# MMI.net
KiCad netlist of a schematic drawn in Altium Designer
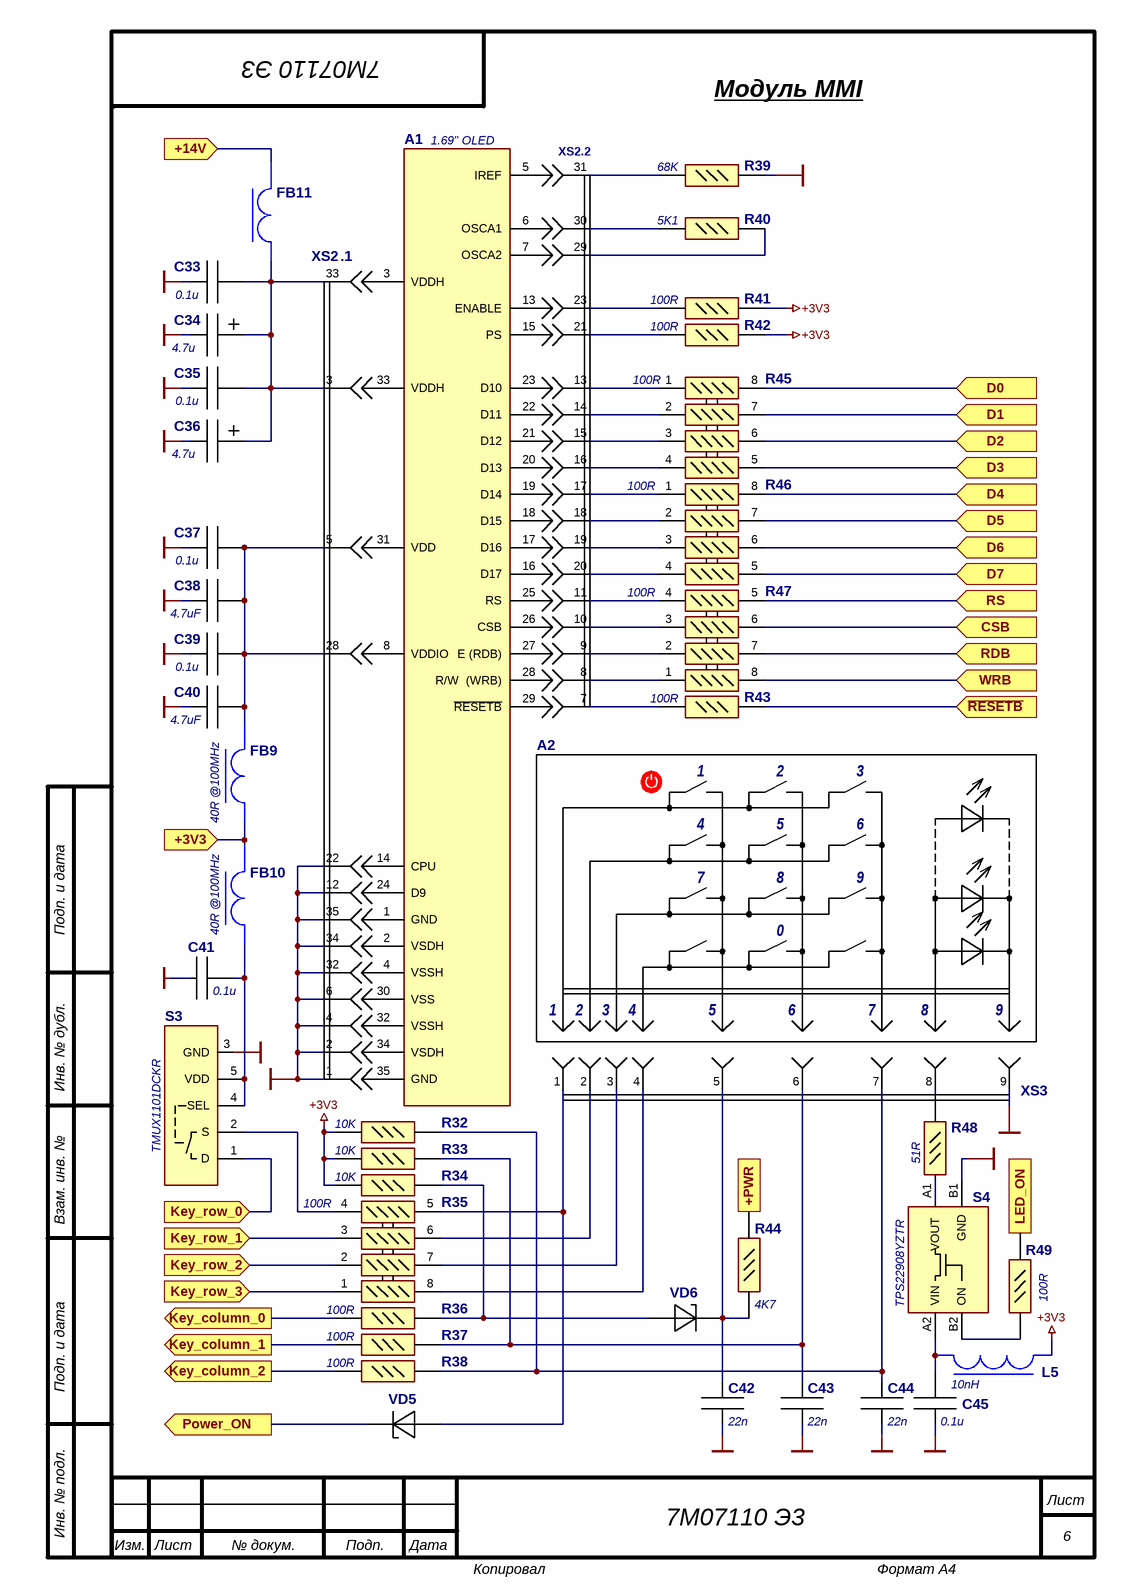
[diagram p0: Модуль MMI.SchDoc]

(export (version "E")
  (design (tool "Eeschema 10.0.6"))
  (components
    (comp (ref "A1")
      (value "1.69\" OLED")
      (fields (field (name "MANUFACTURER_PART_NUMBER") "NHD-1.69-160128G"))
      (libsource (lib "Other") (part "NHD-1.69-160128G"))
    )
    (comp (ref "A2")
      (value "~")
      (fields (field (name "MANUFACTURER_PART_NUMBER") "Клавиатура 5042 ТЕИЯ.464511.002 ТЗ"))
      (libsource (lib "Other") (part "Клавиатура 3x4 (Заказ №...)"))
    )
    (comp (ref "C33")
      (value "0.1u")
      (footprint ":CAP0402 100x50x50")
      (description "±10% 25V Ceramic Capacitor X7R 0402 (1005 Metric)")
      (fields
        (field (name "MANUFACTURER_PART_NUMBER") "GRM155R71E104KE14J")
        (field (name "MOUSER PART NUMBER") "81-GRM155R71E104KE4J")
      )
      (libsource (lib "Capacitors 0402") (part "GRM155R71E104KE14J"))
    )
    (comp (ref "C34")
      (value "4.7u")
      (footprint ":CAP1206 C3216-18")
      (description "4.7µF Molded Tantalum Capacitors 25V 1206 (3216 Metric) 50mOhm")
      (fields (field (name "MANUFACTURER_PART_NUMBER") "T491A475K025AT"))
      (libsource (lib "Capacitors 1206") (part "T491A475K025AT"))
    )
    (comp (ref "C35")
      (value "0.1u")
      (footprint ":CAP0402 100x50x50")
      (description "±10% 25V Ceramic Capacitor X7R 0402 (1005 Metric)")
      (fields
        (field (name "MANUFACTURER_PART_NUMBER") "GRM155R71E104KE14J")
        (field (name "MOUSER PART NUMBER") "81-GRM155R71E104KE4J")
      )
      (libsource (lib "Capacitors 0402") (part "GRM155R71E104KE14J"))
    )
    (comp (ref "C36")
      (value "4.7u")
      (footprint ":CAP1206 C3216-18")
      (description "4.7µF Molded Tantalum Capacitors 25V 1206 (3216 Metric) 50mOhm")
      (fields (field (name "MANUFACTURER_PART_NUMBER") "T491A475K025AT"))
      (libsource (lib "Capacitors 1206") (part "T491A475K025AT"))
    )
    (comp (ref "C37")
      (value "0.1u")
      (footprint ":CAP0402 100x50x50")
      (description "±10% 25V Ceramic Capacitor X7R 0402 (1005 Metric)")
      (fields
        (field (name "MANUFACTURER_PART_NUMBER") "GRM155R71E104KE14J")
        (field (name "MOUSER PART NUMBER") "81-GRM155R71E104KE4J")
      )
      (libsource (lib "Capacitors 0402") (part "GRM155R71E104KE14J"))
    )
    (comp (ref "C38")
      (value "4.7uF")
      (footprint ":CAP0805 C2012X125")
      (description "CAP CER 4.7uF 25V X7R 0805")
      (fields (field (name "MANUFACTURER_PART_NUMBER") "GRM21BZ71E475KE15L"))
      (libsource (lib "Capacitors 0805") (part "GRM21BZ71E475KE15L"))
    )
    (comp (ref "C39")
      (value "0.1u")
      (footprint ":CAP0402 100x50x50")
      (description "±10% 25V Ceramic Capacitor X7R 0402 (1005 Metric)")
      (fields
        (field (name "MANUFACTURER_PART_NUMBER") "GRM155R71E104KE14J")
        (field (name "MOUSER PART NUMBER") "81-GRM155R71E104KE4J")
      )
      (libsource (lib "Capacitors 0402") (part "GRM155R71E104KE14J"))
    )
    (comp (ref "C40")
      (value "4.7uF")
      (footprint ":CAP0805 C2012X125")
      (description "CAP CER 4.7uF 25V X7R 0805")
      (fields (field (name "MANUFACTURER_PART_NUMBER") "GRM21BZ71E475KE15L"))
      (libsource (lib "Capacitors 0805") (part "GRM21BZ71E475KE15L"))
    )
    (comp (ref "C41")
      (value "0.1u")
      (footprint ":CAP0402 100x50x50")
      (description "±10% 25V Ceramic Capacitor X7R 0402 (1005 Metric)")
      (fields
        (field (name "MANUFACTURER_PART_NUMBER") "GRM155R71E104KE14J")
        (field (name "MOUSER PART NUMBER") "81-GRM155R71E104KE4J")
      )
      (libsource (lib "Capacitors 0402") (part "GRM155R71E104KE14J"))
    )
    (comp (ref "C42")
      (value "22n")
      (footprint ":CAP0402 100x50x50")
      (description "CAP CER  25V X7R 0402")
      (fields (field (name "MANUFACTURER_PART_NUMBER") "GCM155R71E223KA55D"))
      (libsource (lib "Capacitors 0402") (part "GCM155R71E223KA55D"))
    )
    (comp (ref "C43")
      (value "22n")
      (footprint ":CAP0402 100x50x50")
      (description "CAP CER  25V X7R 0402")
      (fields (field (name "MANUFACTURER_PART_NUMBER") "GCM155R71E223KA55D"))
      (libsource (lib "Capacitors 0402") (part "GCM155R71E223KA55D"))
    )
    (comp (ref "C44")
      (value "22n")
      (footprint ":CAP0402 100x50x50")
      (description "CAP CER  25V X7R 0402")
      (fields (field (name "MANUFACTURER_PART_NUMBER") "GCM155R71E223KA55D"))
      (libsource (lib "Capacitors 0402") (part "GCM155R71E223KA55D"))
    )
    (comp (ref "C45")
      (value "0.1u")
      (footprint ":CAP0402 100x50x50")
      (description "±10% 25V Ceramic Capacitor X7R 0402 (1005 Metric)")
      (fields
        (field (name "MANUFACTURER_PART_NUMBER") "GRM155R71E104KE14J")
        (field (name "MOUSER PART NUMBER") "81-GRM155R71E104KE4J")
      )
      (libsource (lib "Capacitors 0402") (part "GRM155R71E104KE14J"))
    )
    (comp (ref "FB9")
      (value "40R @100MHz")
      (footprint ":FER MMZ1005Y400CTD25")
      (description "40 Ohms @ 100MHz 1 Signal Line Ferrite Bead 0402 (1005 Metric) 550mA 100mOhm")
      (fields
        (field (name "MANUFACTURER_PART_NUMBER") "MMZ1005Y400CTD25")
        (field (name "MOUSER PART NUMBER") "810-MMZ1005Y400CTD25")
      )
      (libsource (lib "Ferrite Bead") (part "MMZ1005Y400CTD25"))
    )
    (comp (ref "FB10")
      (value "40R @100MHz")
      (footprint ":FER MMZ1005Y400CTD25")
      (description "40 Ohms @ 100MHz 1 Signal Line Ferrite Bead 0402 (1005 Metric) 550mA 100mOhm")
      (fields
        (field (name "MANUFACTURER_PART_NUMBER") "MMZ1005Y400CTD25")
        (field (name "MOUSER PART NUMBER") "810-MMZ1005Y400CTD25")
      )
      (libsource (lib "Ferrite Bead") (part "MMZ1005Y400CTD25"))
    )
    (comp (ref "FB11")
      (value "40R @100MHz")
      (footprint ":FER MMZ1005Y400CTD25")
      (description "40 Ohms @ 100MHz 1 Signal Line Ferrite Bead 0402 (1005 Metric) 550mA 100mOhm")
      (fields
        (field (name "MANUFACTURER_PART_NUMBER") "MMZ1005Y400CTD25")
        (field (name "MOUSER PART NUMBER") "810-MMZ1005Y400CTD25")
      )
      (libsource (lib "Ferrite Bead") (part "MMZ1005Y400CTD25"))
    )
    (comp (ref "L5")
      (value "10nH")
      (footprint ":IND 0402")
      (description "Unshielded Multilayer Inductor 0402 5%")
      (fields (field (name "MANUFACTURER_PART_NUMBER") "LQG15HN10NJ02D"))
      (libsource (lib "Inductance 0402") (part "LQG15HN10NJ02D"))
    )
    (comp (ref "R32")
      (value "RC0402FR-07")
      (footprint ":RES0402")
      (fields (field (name "MANUFACTURER_PART_NUMBER (PART 2: VALUE)") "10K"))
      (libsource (lib "") (part "RC0402FR-07_1"))
    )
    (comp (ref "R33")
      (value "RC0402FR-07")
      (footprint ":RES0402")
      (fields (field (name "MANUFACTURER_PART_NUMBER (PART 2: VALUE)") "10K"))
      (libsource (lib "") (part "RC0402FR-07_1"))
    )
    (comp (ref "R34")
      (value "RC0402FR-07")
      (footprint ":RES0402")
      (fields (field (name "MANUFACTURER_PART_NUMBER (PART 2: VALUE)") "10K"))
      (libsource (lib "") (part "RC0402FR-07_1"))
    )
    (comp (ref "R35")
      (value "100R")
      (footprint ":RES0402x4")
      (fields
        (field (name "MANUFACTURER_PART_NUMBER") "EXB-N8V101JX")
        (field (name "MOUSER PART NUMBER") "667-EXB-N8V101JX")
      )
      (libsource (lib "") (part "EXB-N8V101JX_1"))
    )
    (comp (ref "R36")
      (value "RC0402FR-07")
      (footprint ":RES0402")
      (fields (field (name "MANUFACTURER_PART_NUMBER (PART 2: VALUE)") "100R"))
      (libsource (lib "Resistors 0402") (part "RC0402FR-07"))
    )
    (comp (ref "R37")
      (value "RC0402FR-07")
      (footprint ":RES0402")
      (fields (field (name "MANUFACTURER_PART_NUMBER (PART 2: VALUE)") "100R"))
      (libsource (lib "Resistors 0402") (part "RC0402FR-07"))
    )
    (comp (ref "R38")
      (value "RC0402FR-07")
      (footprint ":RES0402")
      (fields (field (name "MANUFACTURER_PART_NUMBER (PART 2: VALUE)") "100R"))
      (libsource (lib "Resistors 0402") (part "RC0402FR-07"))
    )
    (comp (ref "R39")
      (value "RC0402FR-07")
      (footprint ":RES0402")
      (fields (field (name "MANUFACTURER_PART_NUMBER (PART 2: VALUE)") "68K"))
      (libsource (lib "Resistors 0402") (part "RC0402FR-07"))
    )
    (comp (ref "R40")
      (value "RC0402FR-07")
      (footprint ":RES0402")
      (fields (field (name "MANUFACTURER_PART_NUMBER (PART 2: VALUE)") "5K1"))
      (libsource (lib "Resistors 0402") (part "RC0402FR-07"))
    )
    (comp (ref "R41")
      (value "RC0402FR-07")
      (footprint ":RES0402")
      (fields (field (name "MANUFACTURER_PART_NUMBER (PART 2: VALUE)") "100R"))
      (libsource (lib "Resistors 0402") (part "RC0402FR-07"))
    )
    (comp (ref "R42")
      (value "RC0402FR-07")
      (footprint ":RES0402")
      (fields (field (name "MANUFACTURER_PART_NUMBER (PART 2: VALUE)") "100R"))
      (libsource (lib "Resistors 0402") (part "RC0402FR-07"))
    )
    (comp (ref "R43")
      (value "RC0402FR-07")
      (footprint ":RES0402")
      (fields (field (name "MANUFACTURER_PART_NUMBER (PART 2: VALUE)") "100R"))
      (libsource (lib "Resistors 0402") (part "RC0402FR-07"))
    )
    (comp (ref "R44")
      (value "RC0402FR-07")
      (footprint ":RES0402")
      (fields (field (name "MANUFACTURER_PART_NUMBER (PART 2: VALUE)") "4K7"))
      (libsource (lib "") (part "RC0402FR-07_2"))
    )
    (comp (ref "R45")
      (value "100R")
      (footprint ":RES0402x4")
      (fields
        (field (name "MANUFACTURER_PART_NUMBER") "EXB-N8V101JX")
        (field (name "MOUSER PART NUMBER") "667-EXB-N8V101JX")
      )
      (libsource (lib "Resistors Arrays") (part "EXB-N8V101JX"))
    )
    (comp (ref "R46")
      (value "100R")
      (footprint ":RES0402x4")
      (fields
        (field (name "MANUFACTURER_PART_NUMBER") "EXB-N8V101JX")
        (field (name "MOUSER PART NUMBER") "667-EXB-N8V101JX")
      )
      (libsource (lib "Resistors Arrays") (part "EXB-N8V101JX"))
    )
    (comp (ref "R47")
      (value "100R")
      (footprint ":RES0402x4")
      (fields
        (field (name "MANUFACTURER_PART_NUMBER") "EXB-N8V101JX")
        (field (name "MOUSER PART NUMBER") "667-EXB-N8V101JX")
      )
      (libsource (lib "") (part "EXB-N8V101JX_1"))
    )
    (comp (ref "R48")
      (value "RC0402FR-07")
      (footprint ":RES0402")
      (fields (field (name "MANUFACTURER_PART_NUMBER (PART 2: VALUE)") "51R"))
      (libsource (lib "") (part "RC0402FR-07_2"))
    )
    (comp (ref "R49")
      (value "RC0402FR-07")
      (footprint ":RES0402")
      (fields (field (name "MANUFACTURER_PART_NUMBER (PART 2: VALUE)") "100R"))
      (libsource (lib "") (part "RC0402FR-07_2"))
    )
    (comp (ref "S3")
      (value "TMUX1101DCKR")
      (footprint ":SC70 (5) P200X125X10")
      (description "SPST Switch Bidir. 1.8 Ω 30mA 300MHz")
      (fields (field (name "MOUSER PART NUMBER") "595-TMUX1101DCKR"))
      (libsource (lib "Switching and Relays") (part "TMUX1101DCKR"))
    )
    (comp (ref "S4")
      (value "TPS22908YZTR")
      (footprint ":BGA4 P90X90X50")
      (description "SPST Switch 3.6-V, 1-A, 28-mΩ")
      (fields (field (name "MOUSER PART NUMBER") "595-TPS22908YZTR"))
      (libsource (lib "Switching and Relays") (part "TPS22908YZTR"))
    )
    (comp (ref "VD5")
      (value "30V 0.1A")
      (footprint ":DIODE SOD-923F")
      (description "Diodes Schottky 0402 30V 0.1A")
      (fields
        (field (name "MANUFACTURER_PART_NUMBER") "CDBQR0130R")
        (field (name "MOUSER PART NUMBER") "750-CDBQR0130R")
      )
      (libsource (lib "Diodes 0402") (part "CDBQR0130R"))
    )
    (comp (ref "VD6")
      (value "30V 0.1A")
      (footprint ":DIODE SOD-923F")
      (description "Diodes Schottky 0402 30V 0.1A")
      (fields
        (field (name "MANUFACTURER_PART_NUMBER") "CDBQR0130R")
        (field (name "MOUSER PART NUMBER") "750-CDBQR0130R")
      )
      (libsource (lib "Diodes 0402") (part "CDBQR0130R"))
    )
    (comp (ref "XS2")
      (value "0541043531")
      (footprint "ZIK lib:541043531")
      (description "Rotary Backlock Connector 35-pin 0.5mm Pitch, Top side Contact")
      (fields (field (name "MOUSER2 PART NUMBER") "538-54104-3531"))
      (libsource (lib "Connectors") (part "0541043531"))
    )
    (comp (ref "XS3")
      (value "XF3M-0915-1B")
      (footprint ":CON XF3M-0915-1B")
      (description "Rotary Backlock Connector 35-pin 0.5mm Pitch, Dual sided Contact")
      (libsource (lib "Connectors") (part "XF3M-0915-1B"))
    )
  )
  (nets
    (net (code "1") (name "+3V3") (class "Default")
      (node (ref "FB10") (pin "2") (pinfunction "2_2") (pintype "passive"))
      (node (ref "FB9") (pin "1") (pinfunction "1_1") (pintype "passive"))
      (node (ref "L5") (pin "2") (pinfunction "2_2") (pintype "passive"))
      (node (ref "R32") (pin "2") (pinfunction "2_2") (pintype "passive"))
      (node (ref "R33") (pin "2") (pinfunction "2_2") (pintype "passive"))
      (node (ref "R34") (pin "2") (pinfunction "2_2") (pintype "passive"))
      (node (ref "R41") (pin "2") (pinfunction "2_2") (pintype "passive"))
      (node (ref "R42") (pin "2") (pinfunction "2_2") (pintype "passive"))
    )
    (net (code "2") (name "/+14V") (class "Default")
      (node (ref "FB11") (pin "2") (pinfunction "2_2") (pintype "passive"))
    )
    (net (code "3") (name "/+PWR") (class "Default")
      (node (ref "R44") (pin "1") (pinfunction "1_1") (pintype "passive"))
    )
    (net (code "4") (name "/CSB") (class "Default")
      (node (ref "R47") (pin "6") (pinfunction "6_6") (pintype "passive"))
    )
    (net (code "5") (name "/D0") (class "Default")
      (node (ref "R45") (pin "8") (pinfunction "8_8") (pintype "passive"))
    )
    (net (code "6") (name "/D1") (class "Default")
      (node (ref "R45") (pin "7") (pinfunction "7_7") (pintype "passive"))
    )
    (net (code "7") (name "/D2") (class "Default")
      (node (ref "R45") (pin "6") (pinfunction "6_6") (pintype "passive"))
    )
    (net (code "8") (name "/D3") (class "Default")
      (node (ref "R45") (pin "5") (pinfunction "5_5") (pintype "passive"))
    )
    (net (code "9") (name "/D4") (class "Default")
      (node (ref "R46") (pin "8") (pinfunction "8_8") (pintype "passive"))
    )
    (net (code "10") (name "/D5") (class "Default")
      (node (ref "R46") (pin "7") (pinfunction "7_7") (pintype "passive"))
    )
    (net (code "11") (name "/D6") (class "Default")
      (node (ref "R46") (pin "6") (pinfunction "6_6") (pintype "passive"))
    )
    (net (code "12") (name "/D7") (class "Default")
      (node (ref "R46") (pin "5") (pinfunction "5_5") (pintype "passive"))
    )
    (net (code "13") (name "/Key_column_0") (class "Default")
      (node (ref "R36") (pin "1") (pinfunction "1_1") (pintype "passive"))
    )
    (net (code "14") (name "/Key_column_1") (class "Default")
      (node (ref "R37") (pin "1") (pinfunction "1_1") (pintype "passive"))
    )
    (net (code "15") (name "/Key_column_2") (class "Default")
      (node (ref "R38") (pin "1") (pinfunction "1_1") (pintype "passive"))
    )
    (net (code "16") (name "/Key_row_0") (class "Default")
      (node (ref "S3") (pin "1") (pinfunction "D_1") (pintype "passive"))
    )
    (net (code "17") (name "/Key_row_1") (class "Default")
      (node (ref "R35") (pin "3") (pinfunction "3_3") (pintype "passive"))
    )
    (net (code "18") (name "/Key_row_2") (class "Default")
      (node (ref "R35") (pin "2") (pinfunction "2_2") (pintype "passive"))
    )
    (net (code "19") (name "/Key_row_3") (class "Default")
      (node (ref "R35") (pin "1") (pinfunction "1_1") (pintype "passive"))
    )
    (net (code "20") (name "/LED_ON") (class "Default")
      (node (ref "R49") (pin "1") (pinfunction "1_1") (pintype "passive"))
    )
    (net (code "21") (name "/Power_ON") (class "Default")
      (node (ref "VD5") (pin "1") (pinfunction "K_1") (pintype "passive"))
    )
    (net (code "22") (name "/RDB") (class "Default")
      (node (ref "R47") (pin "7") (pinfunction "7_7") (pintype "passive"))
    )
    (net (code "23") (name "/RS") (class "Default")
      (node (ref "R47") (pin "5") (pinfunction "5_5") (pintype "passive"))
    )
    (net (code "24") (name "/WRB") (class "Default")
      (node (ref "R47") (pin "8") (pinfunction "8_8") (pintype "passive"))
    )
    (net (code "25") (name "/~{RESETB}") (class "Default")
      (node (ref "R43") (pin "2") (pinfunction "2_2") (pintype "passive"))
    )
    (net (code "26") (name "GND") (class "Default")
      (node (ref "C33") (pin "1") (pinfunction "1_1") (pintype "passive"))
      (node (ref "C34") (pin "2") (pinfunction "2_2") (pintype "passive"))
      (node (ref "C35") (pin "1") (pinfunction "1_1") (pintype "passive"))
      (node (ref "C36") (pin "2") (pinfunction "2_2") (pintype "passive"))
      (node (ref "C37") (pin "1") (pinfunction "1_1") (pintype "passive"))
      (node (ref "C38") (pin "2") (pinfunction "2_2") (pintype "passive"))
      (node (ref "C39") (pin "1") (pinfunction "1_1") (pintype "passive"))
      (node (ref "C40") (pin "2") (pinfunction "2_2") (pintype "passive"))
      (node (ref "C41") (pin "1") (pinfunction "1_1") (pintype "passive"))
      (node (ref "C42") (pin "1") (pinfunction "1_1") (pintype "passive"))
      (node (ref "C43") (pin "1") (pinfunction "1_1") (pintype "passive"))
      (node (ref "C44") (pin "1") (pinfunction "1_1") (pintype "passive"))
      (node (ref "C45") (pin "2") (pinfunction "2_2") (pintype "passive"))
      (node (ref "R39") (pin "2") (pinfunction "2_2") (pintype "passive"))
      (node (ref "S3") (pin "3") (pinfunction "GND_3") (pintype "passive"))
      (node (ref "S4") (pin "B1") (pinfunction "GND_B1") (pintype "passive"))
      (node (ref "XS2") (pin "1") (pintype "passive"))
      (node (ref "XS2") (pin "12") (pintype "passive"))
      (node (ref "XS2") (pin "2") (pintype "passive"))
      (node (ref "XS2") (pin "22") (pintype "passive"))
      (node (ref "XS2") (pin "32") (pintype "passive"))
      (node (ref "XS2") (pin "34") (pintype "passive"))
      (node (ref "XS2") (pin "35") (pintype "passive"))
      (node (ref "XS2") (pin "4") (pintype "passive"))
      (node (ref "XS2") (pin "6") (pintype "passive"))
      (node (ref "XS3") (pin "9") (pinfunction "9_9") (pintype "passive"))
    )
    (net (code "27") (name "Net-(C34-+)") (class "Default")
      (node (ref "C33") (pin "2") (pinfunction "2_2") (pintype "passive"))
      (node (ref "C34") (pin "1") (pinfunction "+_1") (pintype "passive"))
      (node (ref "C35") (pin "2") (pinfunction "2_2") (pintype "passive"))
      (node (ref "C36") (pin "1") (pinfunction "+_1") (pintype "passive"))
      (node (ref "FB11") (pin "1") (pinfunction "1_1") (pintype "passive"))
      (node (ref "XS2") (pin "3") (pintype "passive"))
      (node (ref "XS2") (pin "33") (pintype "passive"))
    )
    (net (code "28") (name "Net-(C37-Pad2)") (class "Default")
      (node (ref "C37") (pin "2") (pinfunction "2_2") (pintype "passive"))
      (node (ref "C38") (pin "1") (pinfunction "1_1") (pintype "passive"))
      (node (ref "C39") (pin "2") (pinfunction "2_2") (pintype "passive"))
      (node (ref "C40") (pin "1") (pinfunction "1_1") (pintype "passive"))
      (node (ref "FB9") (pin "2") (pinfunction "2_2") (pintype "passive"))
      (node (ref "XS2") (pin "28") (pintype "passive"))
      (node (ref "XS2") (pin "5") (pintype "passive"))
    )
    (net (code "29") (name "Net-(C43-Pad2)") (class "Default")
      (node (ref "C43") (pin "2") (pinfunction "2_2") (pintype "passive"))
      (node (ref "R33") (pin "1") (pinfunction "1_1") (pintype "passive"))
      (node (ref "R37") (pin "2") (pinfunction "2_2") (pintype "passive"))
      (node (ref "XS3") (pin "6") (pinfunction "6_6") (pintype "passive"))
    )
    (net (code "30") (name "Net-(C44-Pad2)") (class "Default")
      (node (ref "C44") (pin "2") (pinfunction "2_2") (pintype "passive"))
      (node (ref "R32") (pin "1") (pinfunction "1_1") (pintype "passive"))
      (node (ref "R38") (pin "2") (pinfunction "2_2") (pintype "passive"))
      (node (ref "XS3") (pin "7") (pinfunction "7_7") (pintype "passive"))
    )
    (net (code "31") (name "Net-(R35-Pad7)") (class "Default")
      (node (ref "R35") (pin "7") (pinfunction "7_7") (pintype "passive"))
      (node (ref "XS3") (pin "3") (pinfunction "3_3") (pintype "passive"))
    )
    (net (code "32") (name "Net-(R35-Pad8)") (class "Default")
      (node (ref "R35") (pin "8") (pinfunction "8_8") (pintype "passive"))
      (node (ref "XS3") (pin "4") (pinfunction "4_4") (pintype "passive"))
    )
    (net (code "33") (name "Net-(R39-Pad1)") (class "Default")
      (node (ref "R39") (pin "1") (pinfunction "1_1") (pintype "passive"))
      (node (ref "XS2") (pin "31") (pintype "passive"))
    )
    (net (code "34") (name "Net-(R40-Pad1)") (class "Default")
      (node (ref "R40") (pin "1") (pinfunction "1_1") (pintype "passive"))
      (node (ref "XS2") (pin "30") (pintype "passive"))
    )
    (net (code "35") (name "Net-(R40-Pad2)") (class "Default")
      (node (ref "R40") (pin "2") (pinfunction "2_2") (pintype "passive"))
      (node (ref "XS2") (pin "29") (pintype "passive"))
    )
    (net (code "36") (name "Net-(R41-Pad1)") (class "Default")
      (node (ref "R41") (pin "1") (pinfunction "1_1") (pintype "passive"))
      (node (ref "XS2") (pin "23") (pintype "passive"))
    )
    (net (code "37") (name "Net-(R42-Pad1)") (class "Default")
      (node (ref "R42") (pin "1") (pinfunction "1_1") (pintype "passive"))
      (node (ref "XS2") (pin "21") (pintype "passive"))
    )
    (net (code "38") (name "Net-(R43-Pad1)") (class "Default")
      (node (ref "R43") (pin "1") (pinfunction "1_1") (pintype "passive"))
      (node (ref "XS2") (pin "7") (pintype "passive"))
    )
    (net (code "39") (name "Net-(R45-Pad1)") (class "Default")
      (node (ref "R45") (pin "1") (pinfunction "1_1") (pintype "passive"))
      (node (ref "XS2") (pin "13") (pintype "passive"))
    )
    (net (code "40") (name "Net-(R45-Pad2)") (class "Default")
      (node (ref "R45") (pin "2") (pinfunction "2_2") (pintype "passive"))
      (node (ref "XS2") (pin "14") (pintype "passive"))
    )
    (net (code "41") (name "Net-(R45-Pad3)") (class "Default")
      (node (ref "R45") (pin "3") (pinfunction "3_3") (pintype "passive"))
      (node (ref "XS2") (pin "15") (pintype "passive"))
    )
    (net (code "42") (name "Net-(R45-Pad4)") (class "Default")
      (node (ref "R45") (pin "4") (pinfunction "4_4") (pintype "passive"))
      (node (ref "XS2") (pin "16") (pintype "passive"))
    )
    (net (code "43") (name "Net-(R46-Pad1)") (class "Default")
      (node (ref "R46") (pin "1") (pinfunction "1_1") (pintype "passive"))
      (node (ref "XS2") (pin "17") (pintype "passive"))
    )
    (net (code "44") (name "Net-(R46-Pad2)") (class "Default")
      (node (ref "R46") (pin "2") (pinfunction "2_2") (pintype "passive"))
      (node (ref "XS2") (pin "18") (pintype "passive"))
    )
    (net (code "45") (name "Net-(R46-Pad3)") (class "Default")
      (node (ref "R46") (pin "3") (pinfunction "3_3") (pintype "passive"))
      (node (ref "XS2") (pin "19") (pintype "passive"))
    )
    (net (code "46") (name "Net-(R46-Pad4)") (class "Default")
      (node (ref "R46") (pin "4") (pinfunction "4_4") (pintype "passive"))
      (node (ref "XS2") (pin "20") (pintype "passive"))
    )
    (net (code "47") (name "Net-(R47-Pad1)") (class "Default")
      (node (ref "R47") (pin "1") (pinfunction "1_1") (pintype "passive"))
      (node (ref "XS2") (pin "8") (pintype "passive"))
    )
    (net (code "48") (name "Net-(R47-Pad2)") (class "Default")
      (node (ref "R47") (pin "2") (pinfunction "2_2") (pintype "passive"))
      (node (ref "XS2") (pin "9") (pintype "passive"))
    )
    (net (code "49") (name "Net-(R47-Pad3)") (class "Default")
      (node (ref "R47") (pin "3") (pinfunction "3_3") (pintype "passive"))
      (node (ref "XS2") (pin "10") (pintype "passive"))
    )
    (net (code "50") (name "Net-(R47-Pad4)") (class "Default")
      (node (ref "R47") (pin "4") (pinfunction "4_4") (pintype "passive"))
      (node (ref "XS2") (pin "11") (pintype "passive"))
    )
    (net (code "51") (name "Net-(R48-Pad1)") (class "Default")
      (node (ref "R48") (pin "1") (pinfunction "1_1") (pintype "passive"))
      (node (ref "XS3") (pin "8") (pinfunction "8_8") (pintype "passive"))
    )
    (net (code "52") (name "Net-(S3-S)") (class "Default")
      (node (ref "R35") (pin "4") (pinfunction "4_4") (pintype "passive"))
      (node (ref "S3") (pin "2") (pinfunction "S_2") (pintype "passive"))
    )
    (net (code "53") (name "Net-(S3-SEL)") (class "Default")
      (node (ref "C41") (pin "2") (pinfunction "2_2") (pintype "passive"))
      (node (ref "FB10") (pin "1") (pinfunction "1_1") (pintype "passive"))
      (node (ref "S3") (pin "4") (pinfunction "SEL_4") (pintype "passive"))
      (node (ref "S3") (pin "5") (pinfunction "VDD_5") (pintype "passive"))
    )
    (net (code "54") (name "Net-(S4-ON)") (class "Default")
      (node (ref "R49") (pin "2") (pinfunction "2_2") (pintype "passive"))
      (node (ref "S4") (pin "B2") (pinfunction "ON_B2") (pintype "passive"))
    )
    (net (code "55") (name "Net-(S4-VIN)") (class "Default")
      (node (ref "C45") (pin "1") (pinfunction "1_1") (pintype "passive"))
      (node (ref "L5") (pin "1") (pinfunction "1_1") (pintype "passive"))
      (node (ref "S4") (pin "A2") (pinfunction "VIN_A2") (pintype "passive"))
    )
    (net (code "56") (name "Net-(S4-VOUT)") (class "Default")
      (node (ref "R48") (pin "2") (pinfunction "2_2") (pintype "passive"))
      (node (ref "S4") (pin "A1") (pinfunction "VOUT_A1") (pintype "passive"))
    )
    (net (code "57") (name "Net-(VD5-A)") (class "Default")
      (node (ref "R35") (pin "5") (pinfunction "5_5") (pintype "passive"))
      (node (ref "VD5") (pin "2") (pinfunction "A_2") (pintype "passive"))
      (node (ref "XS3") (pin "1") (pinfunction "1_1") (pintype "passive"))
    )
    (net (code "58") (name "Net-(VD6-A)") (class "Default")
      (node (ref "R34") (pin "1") (pinfunction "1_1") (pintype "passive"))
      (node (ref "R36") (pin "2") (pinfunction "2_2") (pintype "passive"))
      (node (ref "VD6") (pin "2") (pinfunction "A_2") (pintype "passive"))
    )
    (net (code "59") (name "Net-(VD6-K)") (class "Default")
      (node (ref "C42") (pin "2") (pinfunction "2_2") (pintype "passive"))
      (node (ref "R44") (pin "2") (pinfunction "2_2") (pintype "passive"))
      (node (ref "VD6") (pin "1") (pinfunction "K_1") (pintype "passive"))
      (node (ref "XS3") (pin "5") (pinfunction "5_5") (pintype "passive"))
    )
    (net (code "60") (name "Net-(XS3-ч)") (class "Default")
      (node (ref "R35") (pin "6") (pinfunction "6_6") (pintype "passive"))
      (node (ref "XS3") (pin "2") (pinfunction "ч_2") (pintype "passive"))
    )
    (net (code "61") (name "unconnected-(A1-CPU-Pad14)") (class "Default")
      (node (ref "A1") (pin "14") (pinfunction "CPU_14") (pintype "passive"))
    )
    (net (code "62") (name "unconnected-(A1-CSB-Pad26)") (class "Default")
      (node (ref "A1") (pin "26") (pinfunction "CSB_26") (pintype "passive"))
    )
    (net (code "63") (name "unconnected-(A1-D9-Pad24)") (class "Default")
      (node (ref "A1") (pin "24") (pinfunction "D9_24") (pintype "passive"))
    )
    (net (code "64") (name "unconnected-(A1-D10-Pad23)") (class "Default")
      (node (ref "A1") (pin "23") (pinfunction "D10_23") (pintype "passive"))
    )
    (net (code "65") (name "unconnected-(A1-D11-Pad22)") (class "Default")
      (node (ref "A1") (pin "22") (pinfunction "D11_22") (pintype "passive"))
    )
    (net (code "66") (name "unconnected-(A1-D12-Pad21)") (class "Default")
      (node (ref "A1") (pin "21") (pinfunction "D12_21") (pintype "passive"))
    )
    (net (code "67") (name "unconnected-(A1-D13-Pad20)") (class "Default")
      (node (ref "A1") (pin "20") (pinfunction "D13_20") (pintype "passive"))
    )
    (net (code "68") (name "unconnected-(A1-D14-Pad19)") (class "Default")
      (node (ref "A1") (pin "19") (pinfunction "D14_19") (pintype "passive"))
    )
    (net (code "69") (name "unconnected-(A1-D15-Pad18)") (class "Default")
      (node (ref "A1") (pin "18") (pinfunction "D15_18") (pintype "passive"))
    )
    (net (code "70") (name "unconnected-(A1-D16-Pad17)") (class "Default")
      (node (ref "A1") (pin "17") (pinfunction "D16_17") (pintype "passive"))
    )
    (net (code "71") (name "unconnected-(A1-D17-Pad16)") (class "Default")
      (node (ref "A1") (pin "16") (pinfunction "D17_16") (pintype "passive"))
    )
    (net (code "72") (name "unconnected-(A1-ENABLE-Pad13)") (class "Default")
      (node (ref "A1") (pin "13") (pinfunction "ENABLE_13") (pintype "passive"))
    )
    (net (code "73") (name "unconnected-(A1-E_(RDB)-Pad27)") (class "Default")
      (node (ref "A1") (pin "27") (pinfunction "E_(RDB)_27") (pintype "passive"))
    )
    (net (code "74") (name "unconnected-(A1-GND-Pad1)") (class "Default")
      (node (ref "A1") (pin "1") (pinfunction "GND_1") (pintype "passive"))
    )
    (net (code "75") (name "unconnected-(A1-GND-Pad35)") (class "Default")
      (node (ref "A1") (pin "35") (pinfunction "GND_35") (pintype "passive"))
    )
    (net (code "76") (name "unconnected-(A1-IREF-Pad5)") (class "Default")
      (node (ref "A1") (pin "5") (pinfunction "IREF_5") (pintype "passive"))
    )
    (net (code "77") (name "unconnected-(A1-OSCA1-Pad6)") (class "Default")
      (node (ref "A1") (pin "6") (pinfunction "OSCA1_6") (pintype "passive"))
    )
    (net (code "78") (name "unconnected-(A1-OSCA2-Pad7)") (class "Default")
      (node (ref "A1") (pin "7") (pinfunction "OSCA2_7") (pintype "passive"))
    )
    (net (code "79") (name "unconnected-(A1-PS-Pad15)") (class "Default")
      (node (ref "A1") (pin "15") (pinfunction "PS_15") (pintype "passive"))
    )
    (net (code "80") (name "unconnected-(A1-RS-Pad25)") (class "Default")
      (node (ref "A1") (pin "25") (pinfunction "RS_25") (pintype "passive"))
    )
    (net (code "81") (name "unconnected-(A1-R{slash}W__(WRB)-Pad28)") (class "Default")
      (node (ref "A1") (pin "28") (pinfunction "R/W__(WRB)_28") (pintype "passive"))
    )
    (net (code "82") (name "unconnected-(A1-VDD-Pad31)") (class "Default")
      (node (ref "A1") (pin "31") (pinfunction "VDD_31") (pintype "passive"))
    )
    (net (code "83") (name "unconnected-(A1-VDDH-Pad3)") (class "Default")
      (node (ref "A1") (pin "3") (pinfunction "VDDH_3") (pintype "passive"))
    )
    (net (code "84") (name "unconnected-(A1-VDDH-Pad33)") (class "Default")
      (node (ref "A1") (pin "33") (pinfunction "VDDH_33") (pintype "passive"))
    )
    (net (code "85") (name "unconnected-(A1-VDDIO-Pad8)") (class "Default")
      (node (ref "A1") (pin "8") (pinfunction "VDDIO_8") (pintype "passive"))
    )
    (net (code "86") (name "unconnected-(A1-VSDH-Pad2)") (class "Default")
      (node (ref "A1") (pin "2") (pinfunction "VSDH_2") (pintype "passive"))
    )
    (net (code "87") (name "unconnected-(A1-VSDH-Pad34)") (class "Default")
      (node (ref "A1") (pin "34") (pinfunction "VSDH_34") (pintype "passive"))
    )
    (net (code "88") (name "unconnected-(A1-VSS-Pad30)") (class "Default")
      (node (ref "A1") (pin "30") (pinfunction "VSS_30") (pintype "passive"))
    )
    (net (code "89") (name "unconnected-(A1-VSSH-Pad4)") (class "Default")
      (node (ref "A1") (pin "4") (pinfunction "VSSH_4") (pintype "passive"))
    )
    (net (code "90") (name "unconnected-(A1-VSSH-Pad32)") (class "Default")
      (node (ref "A1") (pin "32") (pinfunction "VSSH_32") (pintype "passive"))
    )
    (net (code "91") (name "unconnected-(A1-~{RESETB}-Pad29)") (class "Default")
      (node (ref "A1") (pin "29") (pinfunction "~{RESETB}_29") (pintype "passive"))
    )
  )
)
